# MINI-STM32.net
KiCad netlist of a schematic drawn in Altium Designer
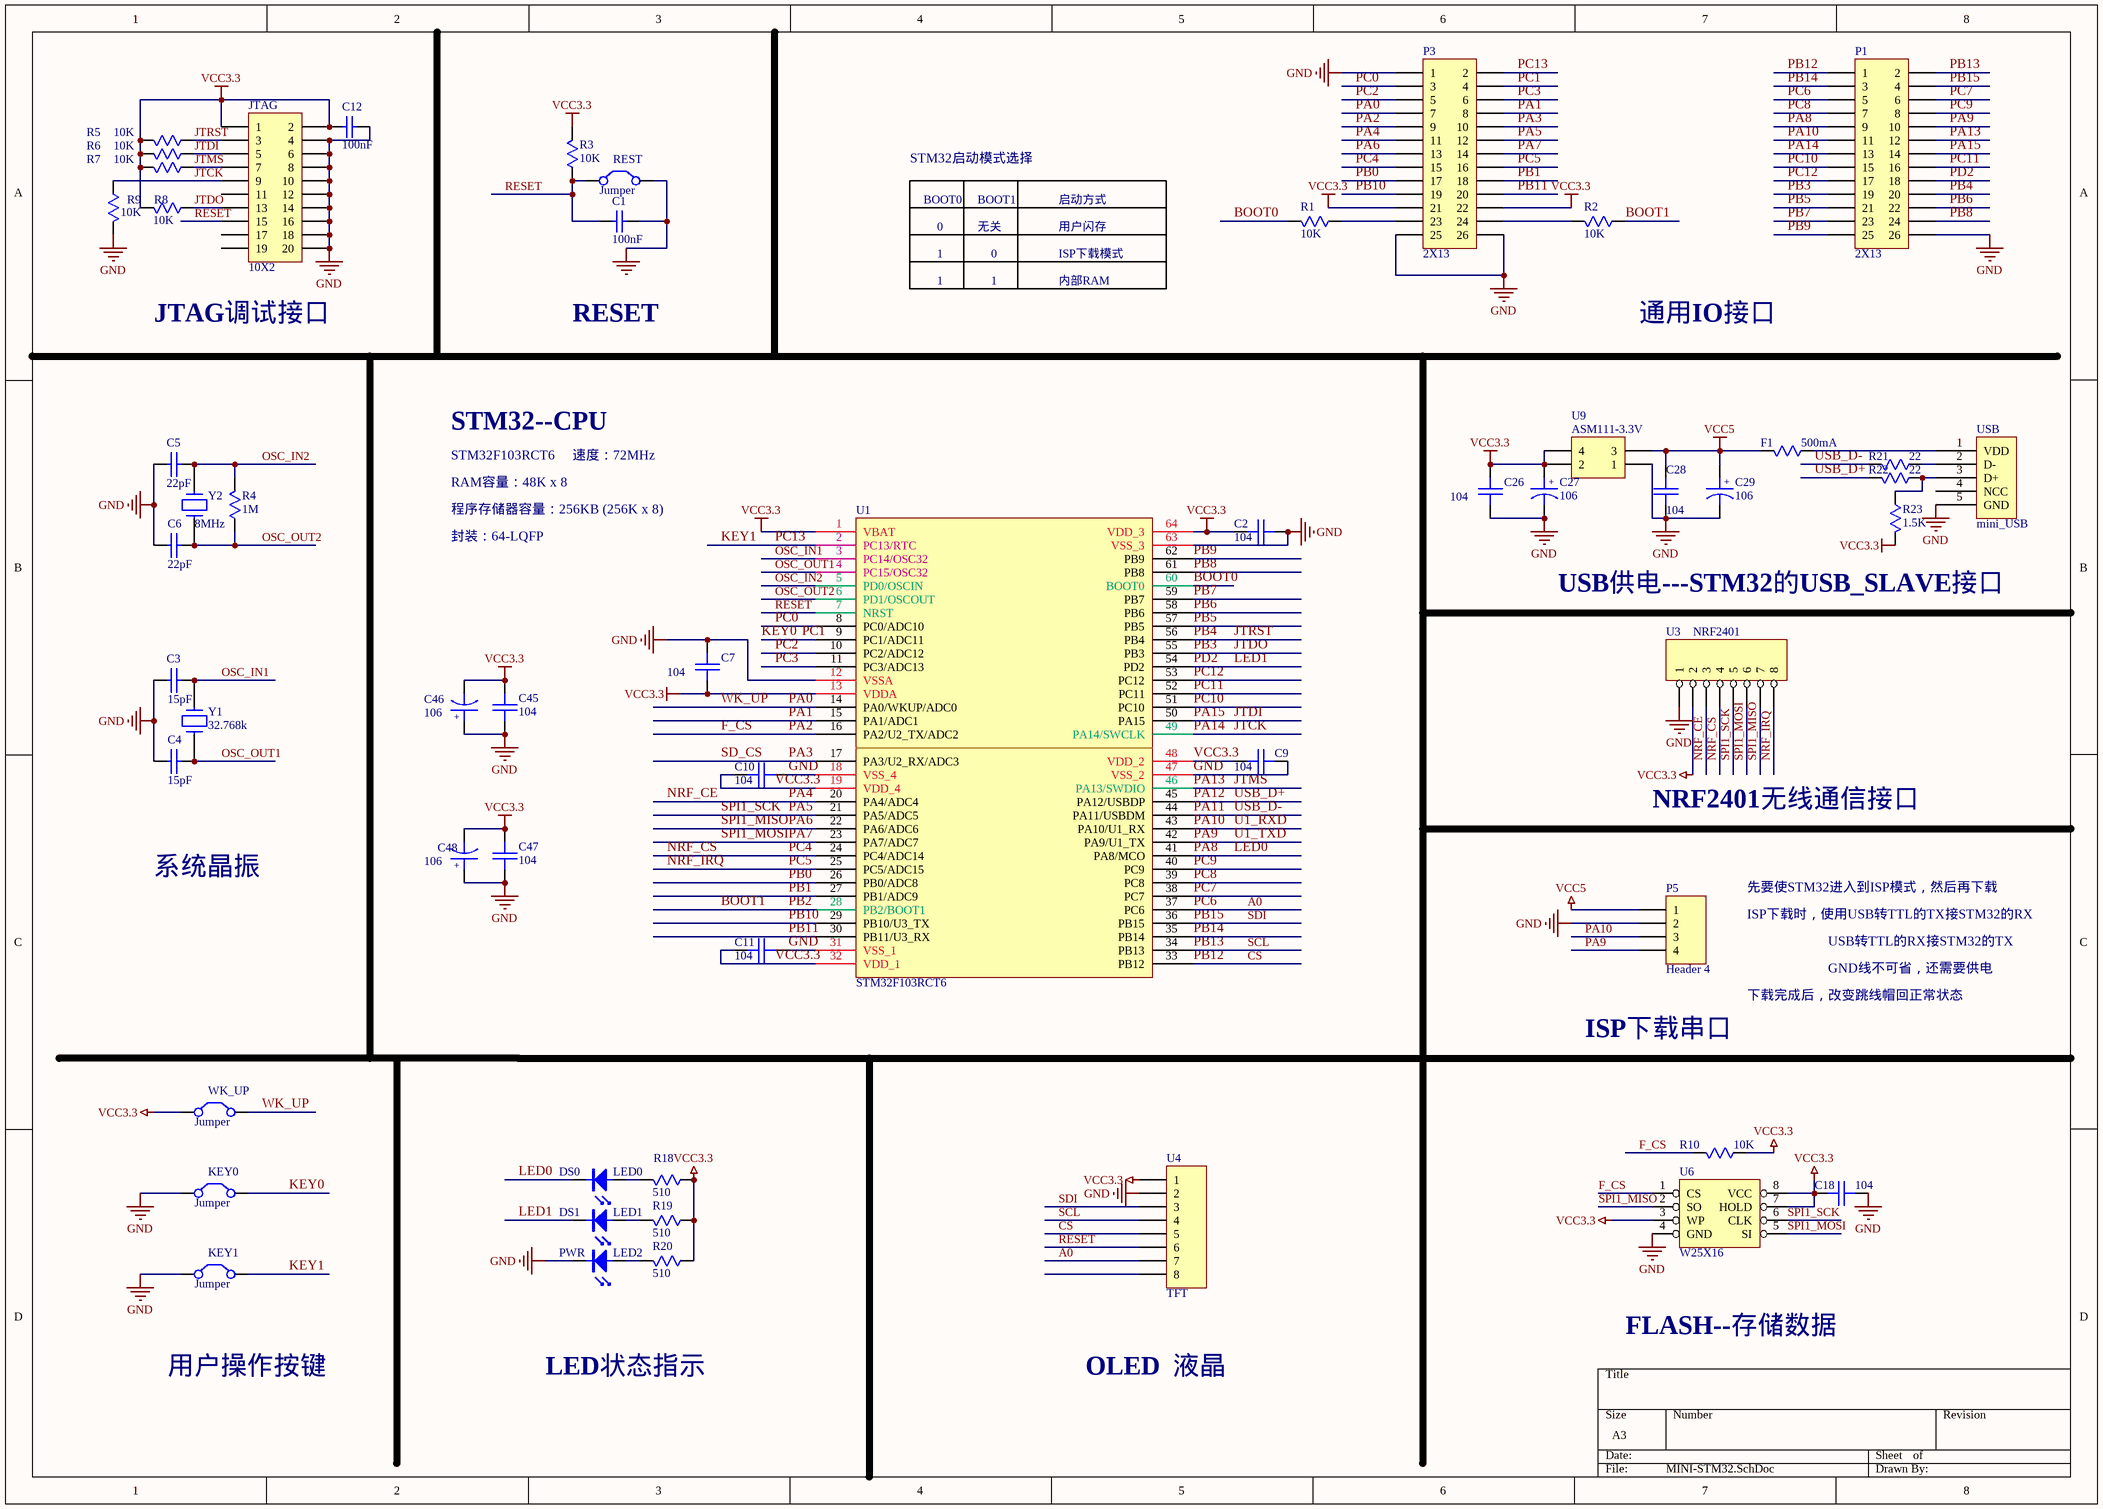
[diagram p0: MINI-STM32.SchDoc]

(export (version "E")
  (design (tool "Eeschema 10.0.6"))
  (components
    (comp (ref "C1")
      (value "100nF")
      (footprint "0603C")
      (description "GRM39 X7R102K50PT")
      (fields (field (name "PUBLISHER") "Altium Limited"))
      (libsource (lib "") (part "CAP_1"))
    )
    (comp (ref "C2") (value "104") (footprint "0603J") (libsource (lib "YT1_SCH_99SE") (part "CAP")))
    (comp (ref "C3")
      (value "15pF")
      (footprint "0603J")
      (description "CAP CHIP 20P 50V(+-5% C0G 0603)")
      (libsource (lib "Miscellaneous Devices") (part "CAP"))
    )
    (comp (ref "C4")
      (value "15pF")
      (footprint "0603J")
      (description "CAP CHIP 20P 50V(+-5% C0G 0603)")
      (libsource (lib "Miscellaneous Devices") (part "CAP"))
    )
    (comp (ref "C5")
      (value "22pF")
      (footprint "0603J")
      (description "CAP CHIP 20P 50V(+-5% C0G 0603)")
      (libsource (lib "Miscellaneous Devices") (part "CAP"))
    )
    (comp (ref "C6")
      (value "22pF")
      (footprint "0603J")
      (description "CAP CHIP 20P 50V(+-5% C0G 0603)")
      (libsource (lib "Miscellaneous Devices") (part "CAP"))
    )
    (comp (ref "C7") (value "104") (footprint "0603J") (libsource (lib "YT1_SCH_99SE") (part "CAP")))
    (comp (ref "C9") (value "104") (footprint "0603J") (libsource (lib "YT1_SCH_99SE") (part "CAP")))
    (comp (ref "C10") (value "104") (footprint "0603J") (libsource (lib "YT1_SCH_99SE") (part "CAP")))
    (comp (ref "C11") (value "104") (footprint "0603J") (libsource (lib "YT1_SCH_99SE") (part "CAP")))
    (comp (ref "C12")
      (value "100nF")
      (footprint "0603C")
      (description "GRM39 X7R102K50PT")
      (fields (field (name "PUBLISHER") "Altium Limited"))
      (libsource (lib "") (part "CAP_1"))
    )
    (comp (ref "C18") (value "104") (footprint "0603J") (libsource (lib "YT1_SCH_99SE") (part "CAP")))
    (comp (ref "C26") (value "104") (footprint "0603J") (libsource (lib "YT1_SCH_99SE") (part "CAP")))
    (comp (ref "C27") (value "106") (footprint "10UF_T") (libsource (lib "YT1_SCH_99SE") (part "CAP2")))
    (comp (ref "C28") (value "104") (footprint "0603J") (libsource (lib "YT1_SCH_99SE") (part "CAP")))
    (comp (ref "C29") (value "106") (footprint "10UF_T") (libsource (lib "YT1_SCH_99SE") (part "CAP2")))
    (comp (ref "C45") (value "104") (footprint "0603J") (libsource (lib "YT1_SCH_99SE") (part "CAP")))
    (comp (ref "C46") (value "106") (footprint "TAN-B") (libsource (lib "YT1_SCH_99SE") (part "CAP2")))
    (comp (ref "C47") (value "104") (footprint "0603J") (libsource (lib "YT1_SCH_99SE") (part "CAP")))
    (comp (ref "C48") (value "106") (footprint "TAN-B") (libsource (lib "YT1_SCH_99SE") (part "CAP2")))
    (comp (ref "F1") (value "500mA") (footprint "C1210") (libsource (lib "YT1_SCH_99SE") (part "RES")))
    (comp (ref "JTAG")
      (value "10X2")
      (footprint "IDC20")
      (description "Header, 10-Pin, Dual row, Right Angle")
      (fields (field (name "PUBLISHER") "Altium Limited"))
      (libsource (lib "Miscellaneous Connectors") (part "Header 10X2H"))
    )
    (comp (ref "KEY0")
      (value "Jumper")
      (footprint "key4")
      (description "Jumper Wire")
      (fields (field (name "PUBLISHER") "Altium Limited"))
      (libsource (lib "Free Documents") (part "Jumper"))
    )
    (comp (ref "KEY1")
      (value "Jumper")
      (footprint "key4")
      (description "Jumper Wire")
      (fields (field (name "PUBLISHER") "Altium Limited"))
      (libsource (lib "Free Documents") (part "Jumper"))
    )
    (comp (ref "LED0") (value "DS0") (footprint "LED0805") (libsource (lib "YT1_SCH_99SE") (part "LED")))
    (comp (ref "LED1") (value "DS1") (footprint "LED0805") (libsource (lib "YT1_SCH_99SE") (part "LED")))
    (comp (ref "LED2") (value "PWR") (footprint "LED0805") (libsource (lib "YT1_SCH_99SE") (part "LED")))
    (comp (ref "P1")
      (value "2X13")
      (footprint "HDR2X13")
      (description "Header, 13-Pin, Dual row")
      (fields (field (name "PUBLISHER") "Altium Limited"))
      (libsource (lib "Miscellaneous Connectors") (part "MHDR2X13"))
    )
    (comp (ref "P3")
      (value "2X13")
      (footprint "HDR2X13")
      (description "Header, 13-Pin, Dual row")
      (fields (field (name "PUBLISHER") "Altium Limited"))
      (libsource (lib "Miscellaneous Connectors") (part "MHDR2X13"))
    )
    (comp (ref "P5")
      (value "Header 4")
      (footprint "HDR1X4")
      (description "Header, 4-Pin")
      (fields (field (name "PUBLISHER") "Altium Limited"))
      (libsource (lib "Miscellaneous Connectors") (part "Header 4"))
    )
    (comp (ref "R1") (value "10K") (footprint "0603J") (libsource (lib "YT1_SCH_99SE") (part "RES")))
    (comp (ref "R2") (value "10K") (footprint "0603J") (libsource (lib "YT1_SCH_99SE") (part "RES")))
    (comp (ref "R3") (value "10K") (footprint "0603J") (libsource (lib "YT1_SCH_99SE") (part "RES")))
    (comp (ref "R4") (value "1M") (footprint "R0603") (libsource (lib "YT1_SCH_99SE") (part "RES")))
    (comp (ref "R5") (value "10K") (footprint "0603J") (libsource (lib "YT1_SCH_99SE") (part "RES")))
    (comp (ref "R6") (value "10K") (footprint "0603J") (libsource (lib "YT1_SCH_99SE") (part "RES")))
    (comp (ref "R7") (value "10K") (footprint "0603J") (libsource (lib "YT1_SCH_99SE") (part "RES")))
    (comp (ref "R8") (value "10K") (footprint "0603J") (libsource (lib "YT1_SCH_99SE") (part "RES")))
    (comp (ref "R9") (value "10K") (footprint "0603J") (libsource (lib "YT1_SCH_99SE") (part "RES")))
    (comp (ref "R10") (value "10K") (footprint "0603J") (libsource (lib "YT1_SCH_99SE") (part "RES")))
    (comp (ref "R18") (value "510") (footprint "0603J") (libsource (lib "YT1_SCH_99SE") (part "RES")))
    (comp (ref "R19") (value "510") (footprint "0603J") (libsource (lib "YT1_SCH_99SE") (part "RES")))
    (comp (ref "R20") (value "510") (footprint "0603J") (libsource (lib "YT1_SCH_99SE") (part "RES")))
    (comp (ref "R21") (value "22") (footprint "0603J") (libsource (lib "YT1_SCH_99SE") (part "RES")))
    (comp (ref "R22") (value "22") (footprint "0603J") (libsource (lib "YT1_SCH_99SE") (part "RES")))
    (comp (ref "R23") (value "1.5K") (footprint "0603J") (libsource (lib "YT1_SCH_99SE") (part "RES")))
    (comp (ref "REST")
      (value "Jumper")
      (footprint "key4")
      (description "Jumper Wire")
      (fields (field (name "PUBLISHER") "Altium Limited"))
      (libsource (lib "Free Documents") (part "Jumper"))
    )
    (comp (ref "U1")
      (value "STM32F103RCT6")
      (footprint "QFP64/P0.5/W12")
      (libsource (lib "YT1_SCH_99SE") (part "STM32F103RBT6"))
    )
    (comp (ref "U3")
      (value "NRF2401")
      (footprint "HDR2X4")
      (description "8 Pin Header")
      (libsource (lib "YT1_SCH_99SE") (part "HEADER 8"))
    )
    (comp (ref "U4")
      (value "TFT")
      (footprint "HDR1X8")
      (description "Header, 8-Pin")
      (libsource (lib "Miscellaneous Connectors") (part "Header 8"))
    )
    (comp (ref "U6") (value "W25X16") (footprint "SOIC8P") (libsource (lib "YT1_SCH_99SE") (part "W25X16")))
    (comp (ref "U9")
      (value "ASM111-3.3V")
      (footprint "Muti-Card-Reader V1.6:SOT223")
      (description "Header, 2-Pin, Dual row, Right Angle")
      (fields (field (name "PUBLISHER") "Altium Limited"))
      (libsource (lib "Miscellaneous Connectors") (part "Header 2X2H"))
    )
    (comp (ref "USB") (value "mini_USB") (footprint "MINIUSB") (libsource (lib "YT1_SCH_99SE") (part "usb")))
    (comp (ref "WK_UP")
      (value "Jumper")
      (footprint "key4")
      (description "Jumper Wire")
      (fields (field (name "PUBLISHER") "Altium Limited"))
      (libsource (lib "Free Documents") (part "Jumper"))
    )
    (comp (ref "Y1")
      (value "32.768k")
      (footprint "32.768k")
      (description "Crystal 8MHz PLUG")
      (libsource (lib "*") (part "CRYSTAL"))
    )
    (comp (ref "Y2")
      (value "8MHz")
      (footprint "smt-xtal")
      (description "Crystal 8MHz PLUG")
      (libsource (lib "*") (part "CRYSTAL"))
    )
  )
  (nets
    (net (code "1") (name "/A0") (class "Default")
      (node (ref "P1") (pin "5") (pinfunction "5_5") (pintype "passive"))
      (node (ref "U1") (pin "37") (pinfunction "PC6_37") (pintype "passive"))
      (node (ref "U4") (pin "7") (pinfunction "7_7") (pintype "passive"))
    )
    (net (code "2") (name "/BOOT0") (class "Default")
      (node (ref "R1") (pin "2") (pinfunction "2_2") (pintype "passive"))
      (node (ref "U1") (pin "60") (pinfunction "BOOT0_60") (pintype "passive"))
    )
    (net (code "3") (name "/BOOT1") (class "Default")
      (node (ref "R2") (pin "1") (pinfunction "1_1") (pintype "passive"))
      (node (ref "U1") (pin "28") (pinfunction "PB2/BOOT1_28") (pintype "passive"))
    )
    (net (code "4") (name "/CS") (class "Default")
      (node (ref "P1") (pin "1") (pinfunction "1_1") (pintype "passive"))
      (node (ref "U1") (pin "33") (pinfunction "PB12_33") (pintype "passive"))
      (node (ref "U4") (pin "5") (pinfunction "5_5") (pintype "passive"))
    )
    (net (code "5") (name "/F_CS") (class "Default")
      (node (ref "P3") (pin "9") (pinfunction "9_9") (pintype "passive"))
      (node (ref "R10") (pin "2") (pinfunction "2_2") (pintype "passive"))
      (node (ref "U1") (pin "16") (pinfunction "PA2/U2_TX/ADC2_16") (pintype "passive"))
      (node (ref "U6") (pin "1") (pinfunction "CS_1") (pintype "passive"))
    )
    (net (code "6") (name "/JTCK") (class "Default")
      (node (ref "JTAG") (pin "9") (pinfunction "9_9") (pintype "passive"))
      (node (ref "P1") (pin "13") (pinfunction "13_13") (pintype "passive"))
      (node (ref "R9") (pin "1") (pinfunction "1_1") (pintype "passive"))
      (node (ref "U1") (pin "49") (pinfunction "PA14/SWCLK_49") (pintype "passive"))
    )
    (net (code "7") (name "/JTDI") (class "Default")
      (node (ref "JTAG") (pin "5") (pinfunction "5_5") (pintype "passive"))
      (node (ref "P1") (pin "14") (pinfunction "14_14") (pintype "passive"))
      (node (ref "R6") (pin "1") (pinfunction "1_1") (pintype "passive"))
      (node (ref "U1") (pin "50") (pinfunction "PA15_50") (pintype "passive"))
    )
    (net (code "8") (name "/JTDO") (class "Default")
      (node (ref "JTAG") (pin "13") (pinfunction "13_13") (pintype "passive"))
      (node (ref "P1") (pin "19") (pinfunction "19_19") (pintype "passive"))
      (node (ref "R8") (pin "1") (pinfunction "1_1") (pintype "passive"))
      (node (ref "U1") (pin "55") (pinfunction "PB3_55") (pintype "passive"))
    )
    (net (code "9") (name "/JTMS") (class "Default")
      (node (ref "JTAG") (pin "7") (pinfunction "7_7") (pintype "passive"))
      (node (ref "P1") (pin "12") (pinfunction "12_12") (pintype "passive"))
      (node (ref "R7") (pin "1") (pinfunction "1_1") (pintype "passive"))
      (node (ref "U1") (pin "46") (pinfunction "PA13/SWDIO_46") (pintype "passive"))
    )
    (net (code "10") (name "/JTRST") (class "Default")
      (node (ref "JTAG") (pin "3") (pinfunction "3_3") (pintype "passive"))
      (node (ref "P1") (pin "20") (pinfunction "20_20") (pintype "passive"))
      (node (ref "R5") (pin "1") (pinfunction "1_1") (pintype "passive"))
      (node (ref "U1") (pin "56") (pinfunction "PB4_56") (pintype "passive"))
    )
    (net (code "11") (name "/KEY0") (class "Default")
      (node (ref "KEY0") (pin "2") (pinfunction "C2_2") (pintype "passive"))
      (node (ref "P3") (pin "4") (pinfunction "4_4") (pintype "passive"))
      (node (ref "U1") (pin "9") (pinfunction "PC1/ADC11_9") (pintype "passive"))
    )
    (net (code "12") (name "/KEY1") (class "Default")
      (node (ref "KEY1") (pin "2") (pinfunction "C2_2") (pintype "passive"))
      (node (ref "P3") (pin "2") (pinfunction "2_2") (pintype "passive"))
      (node (ref "U1") (pin "2") (pinfunction "PC13/RTC_2") (pintype "passive"))
    )
    (net (code "13") (name "/LED0") (class "Default")
      (node (ref "LED0") (pin "K") (pinfunction "2_K") (pintype "passive"))
      (node (ref "P1") (pin "9") (pinfunction "9_9") (pintype "passive"))
      (node (ref "U1") (pin "41") (pinfunction "PA8/MCO_41") (pintype "passive"))
    )
    (net (code "14") (name "/LED1") (class "Default")
      (node (ref "LED1") (pin "K") (pinfunction "2_K") (pintype "passive"))
      (node (ref "P1") (pin "18") (pinfunction "18_18") (pintype "passive"))
      (node (ref "U1") (pin "54") (pinfunction "PD2_54") (pintype "passive"))
    )
    (net (code "15") (name "/NRF_CE") (class "Default")
      (node (ref "P3") (pin "11") (pinfunction "11_11") (pintype "passive"))
      (node (ref "U1") (pin "20") (pinfunction "PA4/ADC4_20") (pintype "passive"))
      (node (ref "U3") (pin "3") (pinfunction "3_3") (pintype "passive"))
    )
    (net (code "16") (name "/NRF_CS") (class "Default")
      (node (ref "P3") (pin "15") (pinfunction "15_15") (pintype "passive"))
      (node (ref "U1") (pin "24") (pinfunction "PC4/ADC14_24") (pintype "passive"))
      (node (ref "U3") (pin "4") (pinfunction "4_4") (pintype "passive"))
    )
    (net (code "17") (name "/NRF_IRQ") (class "Default")
      (node (ref "P3") (pin "16") (pinfunction "16_16") (pintype "passive"))
      (node (ref "U1") (pin "25") (pinfunction "PC5/ADC15_25") (pintype "passive"))
      (node (ref "U3") (pin "8") (pinfunction "8_8") (pintype "passive"))
    )
    (net (code "18") (name "/OSC_IN1") (class "Default")
      (node (ref "C3") (pin "2") (pinfunction "2_2") (pintype "passive"))
      (node (ref "U1") (pin "3") (pinfunction "PC14/OSC32_3") (pintype "passive"))
      (node (ref "Y1") (pin "2") (pinfunction "2_2") (pintype "passive"))
    )
    (net (code "19") (name "/OSC_IN2") (class "Default")
      (node (ref "C5") (pin "2") (pinfunction "2_2") (pintype "passive"))
      (node (ref "R4") (pin "2") (pinfunction "2_2") (pintype "passive"))
      (node (ref "U1") (pin "5") (pinfunction "PD0/OSCIN_5") (pintype "passive"))
      (node (ref "Y2") (pin "1") (pinfunction "1_1") (pintype "passive"))
    )
    (net (code "20") (name "/OSC_OUT1") (class "Default")
      (node (ref "C4") (pin "2") (pinfunction "2_2") (pintype "passive"))
      (node (ref "U1") (pin "4") (pinfunction "PC15/OSC32_4") (pintype "passive"))
      (node (ref "Y1") (pin "1") (pinfunction "1_1") (pintype "passive"))
    )
    (net (code "21") (name "/OSC_OUT2") (class "Default")
      (node (ref "C6") (pin "2") (pinfunction "2_2") (pintype "passive"))
      (node (ref "R4") (pin "1") (pinfunction "1_1") (pintype "passive"))
      (node (ref "U1") (pin "6") (pinfunction "PD1/OSCOUT_6") (pintype "passive"))
      (node (ref "Y2") (pin "2") (pinfunction "2_2") (pintype "passive"))
    )
    (net (code "22") (name "/PA0") (class "Default")
      (node (ref "P3") (pin "7") (pinfunction "7_7") (pintype "passive"))
      (node (ref "U1") (pin "14") (pinfunction "PA0/WKUP/ADC0_14") (pintype "passive"))
      (node (ref "WK_UP") (pin "2") (pinfunction "C2_2") (pintype "passive"))
    )
    (net (code "23") (name "/PA1") (class "Default")
      (node (ref "P3") (pin "8") (pinfunction "8_8") (pintype "passive"))
      (node (ref "U1") (pin "15") (pinfunction "PA1/ADC1_15") (pintype "passive"))
    )
    (net (code "24") (name "/PA3") (class "Default")
      (node (ref "P3") (pin "10") (pinfunction "10_10") (pintype "passive"))
      (node (ref "U1") (pin "17") (pinfunction "PA3/U2_RX/ADC3_17") (pintype "passive"))
    )
    (net (code "25") (name "/PA5") (class "Default")
      (node (ref "P3") (pin "12") (pinfunction "12_12") (pintype "passive"))
      (node (ref "U1") (pin "21") (pinfunction "PA5/ADC5_21") (pintype "passive"))
      (node (ref "U3") (pin "5") (pinfunction "5_5") (pintype "passive"))
      (node (ref "U6") (pin "6") (pinfunction "CLK_6") (pintype "passive"))
    )
    (net (code "26") (name "/PA6") (class "Default")
      (node (ref "P3") (pin "13") (pinfunction "13_13") (pintype "passive"))
      (node (ref "U1") (pin "22") (pinfunction "PA6/ADC6_22") (pintype "passive"))
      (node (ref "U3") (pin "7") (pinfunction "7_7") (pintype "passive"))
      (node (ref "U6") (pin "2") (pinfunction "SO_2") (pintype "passive"))
    )
    (net (code "27") (name "/PA7") (class "Default")
      (node (ref "P3") (pin "14") (pinfunction "14_14") (pintype "passive"))
      (node (ref "U1") (pin "23") (pinfunction "PA7/ADC7_23") (pintype "passive"))
      (node (ref "U3") (pin "6") (pinfunction "6_6") (pintype "passive"))
      (node (ref "U6") (pin "5") (pinfunction "SI_5") (pintype "passive"))
    )
    (net (code "28") (name "/PA9") (class "Default")
      (node (ref "P1") (pin "10") (pinfunction "10_10") (pintype "passive"))
      (node (ref "P5") (pin "4") (pinfunction "4_4") (pintype "passive"))
      (node (ref "U1") (pin "42") (pinfunction "PA9/U1_TX_42") (pintype "passive"))
    )
    (net (code "29") (name "/PA10") (class "Default")
      (node (ref "P1") (pin "11") (pinfunction "11_11") (pintype "passive"))
      (node (ref "P5") (pin "3") (pinfunction "3_3") (pintype "passive"))
      (node (ref "U1") (pin "43") (pinfunction "PA10/U1_RX_43") (pintype "passive"))
    )
    (net (code "30") (name "/PA11") (class "Default")
      (node (ref "R21") (pin "2") (pinfunction "2_2") (pintype "passive"))
      (node (ref "U1") (pin "44") (pinfunction "PA11/USBDM_44") (pintype "passive"))
    )
    (net (code "31") (name "/PA12") (class "Default")
      (node (ref "R22") (pin "2") (pinfunction "2_2") (pintype "passive"))
      (node (ref "U1") (pin "45") (pinfunction "PA12/USBDP_45") (pintype "passive"))
    )
    (net (code "32") (name "/PB0") (class "Default")
      (node (ref "P3") (pin "17") (pinfunction "17_17") (pintype "passive"))
      (node (ref "U1") (pin "26") (pinfunction "PB0/ADC8_26") (pintype "passive"))
    )
    (net (code "33") (name "/PB1") (class "Default")
      (node (ref "P3") (pin "18") (pinfunction "18_18") (pintype "passive"))
      (node (ref "U1") (pin "27") (pinfunction "PB1/ADC9_27") (pintype "passive"))
    )
    (net (code "34") (name "/PB5") (class "Default")
      (node (ref "P1") (pin "21") (pinfunction "21_21") (pintype "passive"))
      (node (ref "U1") (pin "57") (pinfunction "PB5_57") (pintype "passive"))
    )
    (net (code "35") (name "/PB6") (class "Default")
      (node (ref "P1") (pin "22") (pinfunction "22_22") (pintype "passive"))
      (node (ref "U1") (pin "58") (pinfunction "PB6_58") (pintype "passive"))
    )
    (net (code "36") (name "/PB7") (class "Default")
      (node (ref "P1") (pin "23") (pinfunction "23_23") (pintype "passive"))
      (node (ref "U1") (pin "59") (pinfunction "PB7_59") (pintype "passive"))
    )
    (net (code "37") (name "/PB8") (class "Default")
      (node (ref "P1") (pin "24") (pinfunction "24_24") (pintype "passive"))
      (node (ref "U1") (pin "61") (pinfunction "PB8_61") (pintype "passive"))
    )
    (net (code "38") (name "/PB9") (class "Default")
      (node (ref "P1") (pin "25") (pinfunction "25_25") (pintype "passive"))
      (node (ref "U1") (pin "62") (pinfunction "PB9_62") (pintype "passive"))
    )
    (net (code "39") (name "/PB10") (class "Default")
      (node (ref "P3") (pin "19") (pinfunction "19_19") (pintype "passive"))
      (node (ref "U1") (pin "29") (pinfunction "PB10/U3_TX_29") (pintype "passive"))
    )
    (net (code "40") (name "/PB11") (class "Default")
      (node (ref "P3") (pin "20") (pinfunction "20_20") (pintype "passive"))
      (node (ref "U1") (pin "30") (pinfunction "PB11/U3_RX_30") (pintype "passive"))
    )
    (net (code "41") (name "/PB13") (class "Default")
      (node (ref "P1") (pin "2") (pinfunction "2_2") (pintype "passive"))
      (node (ref "U1") (pin "34") (pinfunction "PB13_34") (pintype "passive"))
      (node (ref "U4") (pin "4") (pinfunction "4_4") (pintype "passive"))
    )
    (net (code "42") (name "/PB14") (class "Default")
      (node (ref "P1") (pin "3") (pinfunction "3_3") (pintype "passive"))
      (node (ref "U1") (pin "35") (pinfunction "PB14_35") (pintype "passive"))
    )
    (net (code "43") (name "/PB15") (class "Default")
      (node (ref "P1") (pin "4") (pinfunction "4_4") (pintype "passive"))
      (node (ref "U1") (pin "36") (pinfunction "PB15_36") (pintype "passive"))
      (node (ref "U4") (pin "3") (pinfunction "3_3") (pintype "passive"))
    )
    (net (code "44") (name "/PC0") (class "Default")
      (node (ref "P3") (pin "3") (pinfunction "3_3") (pintype "passive"))
      (node (ref "U1") (pin "8") (pinfunction "PC0/ADC10_8") (pintype "passive"))
    )
    (net (code "45") (name "/PC2") (class "Default")
      (node (ref "P3") (pin "5") (pinfunction "5_5") (pintype "passive"))
      (node (ref "U1") (pin "10") (pinfunction "PC2/ADC12_10") (pintype "passive"))
    )
    (net (code "46") (name "/PC3") (class "Default")
      (node (ref "P3") (pin "6") (pinfunction "6_6") (pintype "passive"))
      (node (ref "U1") (pin "11") (pinfunction "PC3/ADC13_11") (pintype "passive"))
    )
    (net (code "47") (name "/PC7") (class "Default")
      (node (ref "P1") (pin "6") (pinfunction "6_6") (pintype "passive"))
      (node (ref "U1") (pin "38") (pinfunction "PC7_38") (pintype "passive"))
    )
    (net (code "48") (name "/PC8") (class "Default")
      (node (ref "P1") (pin "7") (pinfunction "7_7") (pintype "passive"))
      (node (ref "U1") (pin "39") (pinfunction "PC8_39") (pintype "passive"))
    )
    (net (code "49") (name "/PC9") (class "Default")
      (node (ref "P1") (pin "8") (pinfunction "8_8") (pintype "passive"))
      (node (ref "U1") (pin "40") (pinfunction "PC9_40") (pintype "passive"))
    )
    (net (code "50") (name "/PC10") (class "Default")
      (node (ref "P1") (pin "15") (pinfunction "15_15") (pintype "passive"))
      (node (ref "U1") (pin "51") (pinfunction "PC10_51") (pintype "passive"))
    )
    (net (code "51") (name "/PC11") (class "Default")
      (node (ref "P1") (pin "16") (pinfunction "16_16") (pintype "passive"))
      (node (ref "U1") (pin "52") (pinfunction "PC11_52") (pintype "passive"))
    )
    (net (code "52") (name "/PC12") (class "Default")
      (node (ref "P1") (pin "17") (pinfunction "17_17") (pintype "passive"))
      (node (ref "U1") (pin "53") (pinfunction "PC12_53") (pintype "passive"))
    )
    (net (code "53") (name "/RESET") (class "Default")
      (node (ref "C1") (pin "2") (pinfunction "2_2") (pintype "passive"))
      (node (ref "JTAG") (pin "15") (pinfunction "15_15") (pintype "passive"))
      (node (ref "R3") (pin "1") (pinfunction "1_1") (pintype "passive"))
      (node (ref "REST") (pin "1") (pinfunction "C1_1") (pintype "passive"))
      (node (ref "U1") (pin "7") (pinfunction "NRST_7") (pintype "passive"))
      (node (ref "U4") (pin "6") (pinfunction "6_6") (pintype "passive"))
    )
    (net (code "54") (name "GND") (class "Default")
      (node (ref "C1") (pin "1") (pinfunction "1_1") (pintype "passive"))
      (node (ref "C10") (pin "2") (pinfunction "2_2") (pintype "passive"))
      (node (ref "C11") (pin "2") (pinfunction "2_2") (pintype "passive"))
      (node (ref "C12") (pin "1") (pinfunction "1_1") (pintype "passive"))
      (node (ref "C18") (pin "1") (pinfunction "1_1") (pintype "passive"))
      (node (ref "C2") (pin "2") (pinfunction "2_2") (pintype "passive"))
      (node (ref "C26") (pin "2") (pinfunction "2_2") (pintype "passive"))
      (node (ref "C27") (pin "2") (pinfunction "2_2") (pintype "passive"))
      (node (ref "C28") (pin "2") (pinfunction "2_2") (pintype "passive"))
      (node (ref "C29") (pin "2") (pinfunction "2_2") (pintype "passive"))
      (node (ref "C3") (pin "1") (pinfunction "1_1") (pintype "passive"))
      (node (ref "C4") (pin "1") (pinfunction "1_1") (pintype "passive"))
      (node (ref "C45") (pin "2") (pinfunction "2_2") (pintype "passive"))
      (node (ref "C46") (pin "1") (pinfunction "1_1") (pintype "passive"))
      (node (ref "C47") (pin "2") (pinfunction "2_2") (pintype "passive"))
      (node (ref "C48") (pin "1") (pinfunction "1_1") (pintype "passive"))
      (node (ref "C5") (pin "1") (pinfunction "1_1") (pintype "passive"))
      (node (ref "C6") (pin "1") (pinfunction "1_1") (pintype "passive"))
      (node (ref "C7") (pin "1") (pinfunction "1_1") (pintype "passive"))
      (node (ref "C9") (pin "2") (pinfunction "2_2") (pintype "passive"))
      (node (ref "JTAG") (pin "10") (pinfunction "10_10") (pintype "passive"))
      (node (ref "JTAG") (pin "12") (pinfunction "12_12") (pintype "passive"))
      (node (ref "JTAG") (pin "14") (pinfunction "14_14") (pintype "passive"))
      (node (ref "JTAG") (pin "16") (pinfunction "16_16") (pintype "passive"))
      (node (ref "JTAG") (pin "18") (pinfunction "18_18") (pintype "passive"))
      (node (ref "JTAG") (pin "20") (pinfunction "20_20") (pintype "passive"))
      (node (ref "JTAG") (pin "4") (pinfunction "4_4") (pintype "passive"))
      (node (ref "JTAG") (pin "6") (pinfunction "6_6") (pintype "passive"))
      (node (ref "JTAG") (pin "8") (pinfunction "8_8") (pintype "passive"))
      (node (ref "KEY0") (pin "1") (pinfunction "C1_1") (pintype "passive"))
      (node (ref "KEY1") (pin "1") (pinfunction "C1_1") (pintype "passive"))
      (node (ref "LED2") (pin "K") (pinfunction "2_K") (pintype "passive"))
      (node (ref "P1") (pin "26") (pinfunction "26_26") (pintype "passive"))
      (node (ref "P3") (pin "1") (pinfunction "1_1") (pintype "passive"))
      (node (ref "P3") (pin "25") (pinfunction "25_25") (pintype "passive"))
      (node (ref "P3") (pin "26") (pinfunction "26_26") (pintype "passive"))
      (node (ref "P5") (pin "2") (pinfunction "2_2") (pintype "passive"))
      (node (ref "R9") (pin "2") (pinfunction "2_2") (pintype "passive"))
      (node (ref "REST") (pin "2") (pinfunction "C2_2") (pintype "passive"))
      (node (ref "U1") (pin "12") (pinfunction "VSSA_12") (pintype "passive"))
      (node (ref "U1") (pin "18") (pinfunction "VSS_4_18") (pintype "passive"))
      (node (ref "U1") (pin "31") (pinfunction "VSS_1_31") (pintype "passive"))
      (node (ref "U1") (pin "47") (pinfunction "VSS_2_47") (pintype "passive"))
      (node (ref "U1") (pin "63") (pinfunction "VSS_3_63") (pintype "passive"))
      (node (ref "U3") (pin "1") (pinfunction "1_1") (pintype "passive"))
      (node (ref "U4") (pin "2") (pinfunction "2_2") (pintype "passive"))
      (node (ref "U6") (pin "4") (pinfunction "GND_4") (pintype "passive"))
      (node (ref "U9") (pin "1") (pinfunction "1_1") (pintype "passive"))
      (node (ref "USB") (pin "5") (pinfunction "GND_5") (pintype "passive"))
    )
    (net (code "55") (name "Net-(LED0-1)") (class "Default")
      (node (ref "LED0") (pin "A") (pinfunction "1_A") (pintype "passive"))
      (node (ref "R18") (pin "2") (pinfunction "2_2") (pintype "passive"))
    )
    (net (code "56") (name "Net-(LED1-1)") (class "Default")
      (node (ref "LED1") (pin "A") (pinfunction "1_A") (pintype "passive"))
      (node (ref "R19") (pin "2") (pinfunction "2_2") (pintype "passive"))
    )
    (net (code "57") (name "Net-(LED2-1)") (class "Default")
      (node (ref "LED2") (pin "A") (pinfunction "1_A") (pintype "passive"))
      (node (ref "R20") (pin "2") (pinfunction "2_2") (pintype "passive"))
    )
    (net (code "58") (name "Net-(P3-Pad23)") (class "Default")
      (node (ref "P3") (pin "23") (pinfunction "23_23") (pintype "passive"))
      (node (ref "R1") (pin "1") (pinfunction "1_1") (pintype "passive"))
    )
    (net (code "59") (name "Net-(P3-Pad24)") (class "Default")
      (node (ref "P3") (pin "24") (pinfunction "24_24") (pintype "passive"))
      (node (ref "R2") (pin "2") (pinfunction "2_2") (pintype "passive"))
    )
    (net (code "60") (name "Net-(USB-D+)") (class "Default")
      (node (ref "R22") (pin "1") (pinfunction "1_1") (pintype "passive"))
      (node (ref "R23") (pin "1") (pinfunction "1_1") (pintype "passive"))
      (node (ref "USB") (pin "3") (pinfunction "D+_3") (pintype "passive"))
    )
    (net (code "61") (name "Net-(USB-D-)") (class "Default")
      (node (ref "R21") (pin "1") (pinfunction "1_1") (pintype "passive"))
      (node (ref "USB") (pin "2") (pinfunction "D-_2") (pintype "passive"))
    )
    (net (code "62") (name "Net-(USB-VDD)") (class "Default")
      (node (ref "F1") (pin "1") (pinfunction "1_1") (pintype "passive"))
      (node (ref "USB") (pin "1") (pinfunction "VDD_1") (pintype "passive"))
    )
    (net (code "63") (name "VCC3.3") (class "Default")
      (node (ref "C10") (pin "1") (pinfunction "1_1") (pintype "passive"))
      (node (ref "C11") (pin "1") (pinfunction "1_1") (pintype "passive"))
      (node (ref "C12") (pin "2") (pinfunction "2_2") (pintype "passive"))
      (node (ref "C18") (pin "2") (pinfunction "2_2") (pintype "passive"))
      (node (ref "C2") (pin "1") (pinfunction "1_1") (pintype "passive"))
      (node (ref "C26") (pin "1") (pinfunction "1_1") (pintype "passive"))
      (node (ref "C27") (pin "1") (pinfunction "1_1") (pintype "passive"))
      (node (ref "C45") (pin "1") (pinfunction "1_1") (pintype "passive"))
      (node (ref "C46") (pin "2") (pinfunction "2_2") (pintype "passive"))
      (node (ref "C47") (pin "1") (pinfunction "1_1") (pintype "passive"))
      (node (ref "C48") (pin "2") (pinfunction "2_2") (pintype "passive"))
      (node (ref "C7") (pin "2") (pinfunction "2_2") (pintype "passive"))
      (node (ref "C9") (pin "1") (pinfunction "1_1") (pintype "passive"))
      (node (ref "JTAG") (pin "1") (pinfunction "1_1") (pintype "passive"))
      (node (ref "JTAG") (pin "2") (pinfunction "2_2") (pintype "passive"))
      (node (ref "P3") (pin "21") (pinfunction "21_21") (pintype "passive"))
      (node (ref "P3") (pin "22") (pinfunction "22_22") (pintype "passive"))
      (node (ref "R10") (pin "1") (pinfunction "1_1") (pintype "passive"))
      (node (ref "R18") (pin "1") (pinfunction "1_1") (pintype "passive"))
      (node (ref "R19") (pin "1") (pinfunction "1_1") (pintype "passive"))
      (node (ref "R20") (pin "1") (pinfunction "1_1") (pintype "passive"))
      (node (ref "R23") (pin "2") (pinfunction "2_2") (pintype "passive"))
      (node (ref "R3") (pin "2") (pinfunction "2_2") (pintype "passive"))
      (node (ref "R5") (pin "2") (pinfunction "2_2") (pintype "passive"))
      (node (ref "R6") (pin "2") (pinfunction "2_2") (pintype "passive"))
      (node (ref "R7") (pin "2") (pinfunction "2_2") (pintype "passive"))
      (node (ref "R8") (pin "2") (pinfunction "2_2") (pintype "passive"))
      (node (ref "U1") (pin "1") (pinfunction "VBAT_1") (pintype "passive"))
      (node (ref "U1") (pin "13") (pinfunction "VDDA_13") (pintype "passive"))
      (node (ref "U1") (pin "19") (pinfunction "VDD_4_19") (pintype "passive"))
      (node (ref "U1") (pin "32") (pinfunction "VDD_1_32") (pintype "passive"))
      (node (ref "U1") (pin "48") (pinfunction "VDD_2_48") (pintype "passive"))
      (node (ref "U1") (pin "64") (pinfunction "VDD_3_64") (pintype "passive"))
      (node (ref "U3") (pin "2") (pinfunction "2_2") (pintype "passive"))
      (node (ref "U4") (pin "1") (pinfunction "1_1") (pintype "passive"))
      (node (ref "U6") (pin "3") (pinfunction "WP_3") (pintype "passive"))
      (node (ref "U6") (pin "7") (pinfunction "HOLD_7") (pintype "passive"))
      (node (ref "U6") (pin "8") (pinfunction "VCC_8") (pintype "passive"))
      (node (ref "U9") (pin "2") (pinfunction "2_2") (pintype "passive"))
      (node (ref "U9") (pin "4") (pinfunction "4_4") (pintype "passive"))
      (node (ref "WK_UP") (pin "1") (pinfunction "C1_1") (pintype "passive"))
    )
    (net (code "64") (name "VCC5") (class "Default")
      (node (ref "C28") (pin "1") (pinfunction "1_1") (pintype "passive"))
      (node (ref "C29") (pin "1") (pinfunction "1_1") (pintype "passive"))
      (node (ref "F1") (pin "2") (pinfunction "2_2") (pintype "passive"))
      (node (ref "P5") (pin "1") (pinfunction "1_1") (pintype "passive"))
      (node (ref "U9") (pin "3") (pinfunction "3_3") (pintype "passive"))
    )
    (net (code "65") (name "unconnected-(JTAG-Pad11)") (class "Default")
      (node (ref "JTAG") (pin "11") (pinfunction "11_11") (pintype "passive"))
    )
    (net (code "66") (name "unconnected-(JTAG-Pad17)") (class "Default")
      (node (ref "JTAG") (pin "17") (pinfunction "17_17") (pintype "passive"))
    )
    (net (code "67") (name "unconnected-(JTAG-Pad19)") (class "Default")
      (node (ref "JTAG") (pin "19") (pinfunction "19_19") (pintype "passive"))
    )
    (net (code "68") (name "unconnected-(U4-Pad8)") (class "Default")
      (node (ref "U4") (pin "8") (pinfunction "8_8") (pintype "passive"))
    )
    (net (code "69") (name "unconnected-(USB-NCC-Pad4)") (class "Default")
      (node (ref "USB") (pin "4") (pinfunction "NCC_4") (pintype "passive"))
    )
  )
)
